# SOT23-5.net
KiCad netlist of a schematic drawn in EAGLE
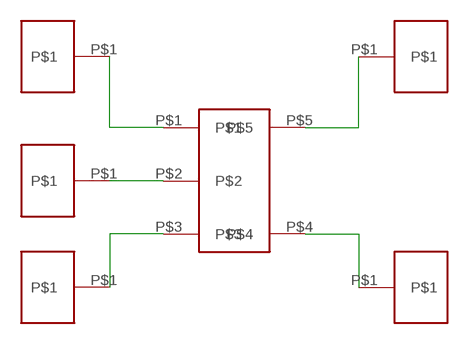
[diagram p0: schematic, sheet 1]

(export (version "E")
  (design (tool "Eeschema 10.0.6"))
  (components
    (comp (ref "U$1")
      (value "SOT23-5")
      (footprint "eagle-import:SOT23-5")
      (libsource (lib "eagle-import") (part "SOT23-5"))
    )
    (comp (ref "U$2")
      (value "PAD")
      (footprint "eagle-import:100MIL_PAD")
      (libsource (lib "eagle-import") (part "PAD"))
    )
    (comp (ref "U$3")
      (value "PAD")
      (footprint "eagle-import:100MIL_PAD")
      (libsource (lib "eagle-import") (part "PAD"))
    )
    (comp (ref "U$4")
      (value "PAD")
      (footprint "eagle-import:100MIL_PAD")
      (libsource (lib "eagle-import") (part "PAD"))
    )
    (comp (ref "U$5")
      (value "PAD")
      (footprint "eagle-import:100MIL_PAD")
      (libsource (lib "eagle-import") (part "PAD"))
    )
    (comp (ref "U$6")
      (value "PAD")
      (footprint "eagle-import:100MIL_PAD")
      (libsource (lib "eagle-import") (part "PAD"))
    )
  )
  (nets
    (net (code "1") (name "Net-(U$1-PadP$1)") (class "Default")
      (node (ref "U$1") (pin "P$1") (pinfunction "P$1_P$1") (pintype "bidirectional"))
      (node (ref "U$3") (pin "P$1") (pinfunction "P$1_P$1") (pintype "bidirectional"))
    )
    (net (code "2") (name "Net-(U$1-PadP$2)") (class "Default")
      (node (ref "U$1") (pin "P$2") (pinfunction "P$2_P$2") (pintype "bidirectional"))
      (node (ref "U$2") (pin "P$1") (pinfunction "P$1_P$1") (pintype "bidirectional"))
    )
    (net (code "3") (name "Net-(U$1-PadP$3)") (class "Default")
      (node (ref "U$1") (pin "P$3") (pinfunction "P$3_P$3") (pintype "bidirectional"))
      (node (ref "U$4") (pin "P$1") (pinfunction "P$1_P$1") (pintype "bidirectional"))
    )
    (net (code "4") (name "Net-(U$1-PadP$4)") (class "Default")
      (node (ref "U$1") (pin "P$4") (pinfunction "P$4_P$4") (pintype "bidirectional"))
      (node (ref "U$5") (pin "P$1") (pinfunction "P$1_P$1") (pintype "bidirectional"))
    )
    (net (code "5") (name "Net-(U$1-PadP$5)") (class "Default")
      (node (ref "U$1") (pin "P$5") (pinfunction "P$5_P$5") (pintype "bidirectional"))
      (node (ref "U$6") (pin "P$1") (pinfunction "P$1_P$1") (pintype "bidirectional"))
    )
  )
)
